# Sheet2.net
KiCad netlist of a schematic drawn in Altium Designer
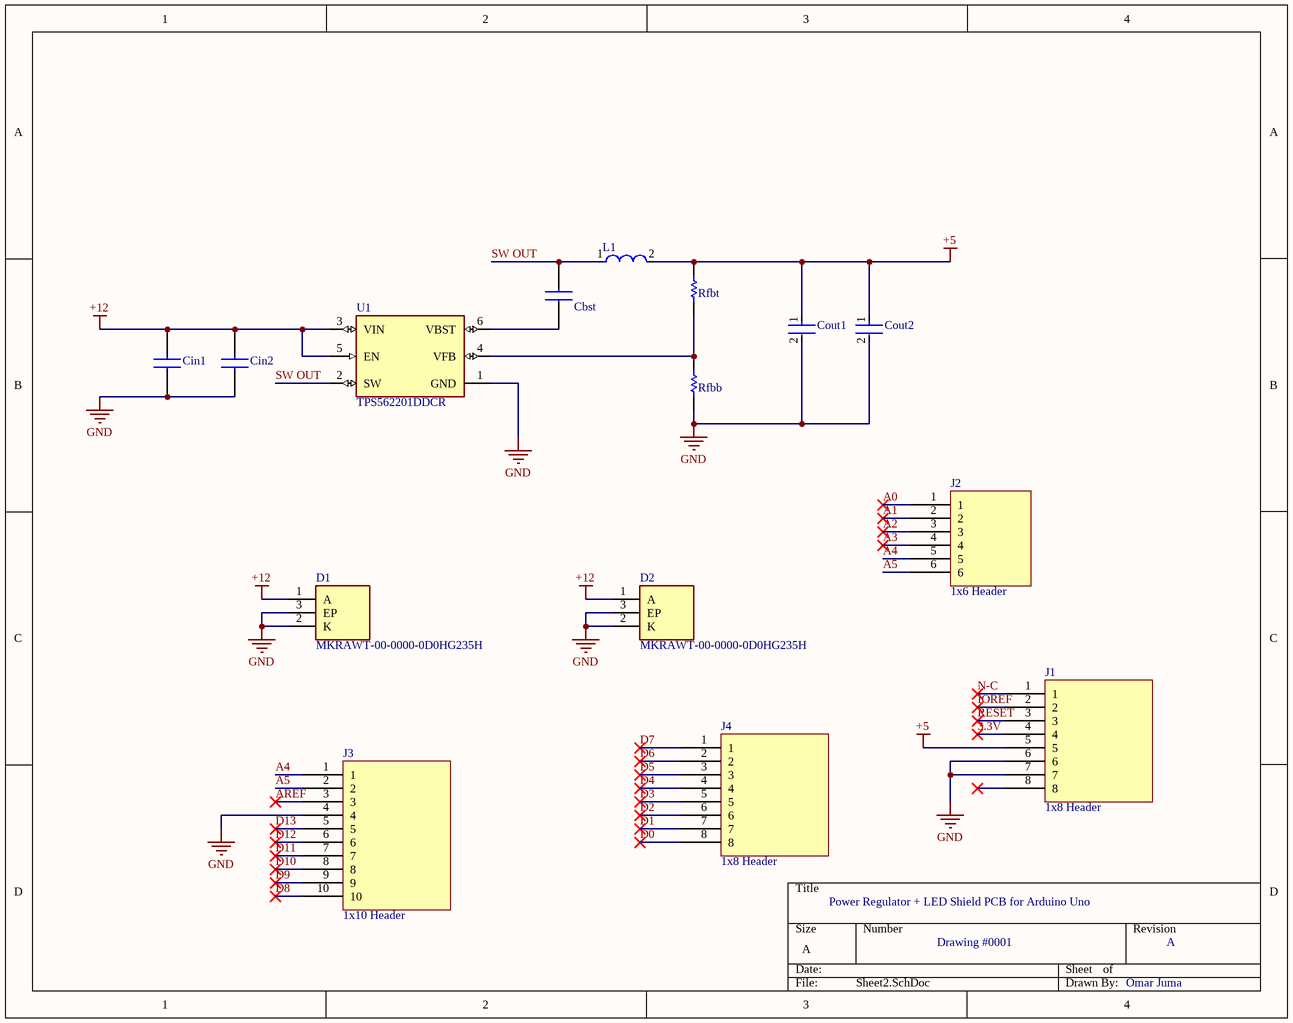
[diagram p0: Sheet2.SchDoc]

(export (version "E")
  (design (tool "Eeschema 10.0.6"))
  (components
    (comp (ref "Cbst")
      (value "08053C104KAT2A")
      (footprint "CAPC2012X94N")
      (libsource (lib "08053C104KAT2A") (part "08053C104KAT2A"))
    )
    (comp (ref "Cin1")
      (value "MSAST219LB5106KTNA01")
      (footprint "CAPC2114X95N")
      (description "Multilayer Ceramic Capacitors MLCC - SMD/SMT 25V 10uF X5R 0805 10%")
      (libsource (lib "MSAST219LB5106KTNA01") (part "MSAST219LB5106KTNA01"))
    )
    (comp (ref "Cin2")
      (value "MSAST219LB5106KTNA01")
      (footprint "CAPC2114X95N")
      (description "Multilayer Ceramic Capacitors MLCC - SMD/SMT 25V 10uF X5R 0805 10%")
      (libsource (lib "MSAST219LB5106KTNA01") (part "MSAST219LB5106KTNA01"))
    )
    (comp (ref "Cout1")
      (value "GRM21BR61A226ME44L")
      (footprint "FP-GRM21B-0_2-e0_2_0_7-IPC_C")
      (description "Chip Multilayer Ceramic Capacitors for General Purpose, 0805, 22uF, X5R, 15%, 20%, 10V")
      (fields (field (name "TOLERANCE") "20%") (field (name "VOLTAGE") "10V"))
      (libsource (lib "Altium Content Vault") (part "b4654b650e69147ec39a6b967a45e02"))
    )
    (comp (ref "Cout2")
      (value "GRM21BR61A226ME44L")
      (footprint "FP-GRM21B-0_2-e0_2_0_7-IPC_C")
      (description "Chip Multilayer Ceramic Capacitors for General Purpose, 0805, 22uF, X5R, 15%, 20%, 10V")
      (fields (field (name "TOLERANCE") "20%") (field (name "VOLTAGE") "10V"))
      (libsource (lib "Altium Content Vault") (part "b4654b650e69147ec39a6b967a45e02"))
    )
    (comp (ref "D1")
      (value "MKRAWT-00-0000-0D0HG235H")
      (footprint "MKRAWT0000000D0HG235H")
      (description "LED Uni-Color White 3500K 80 2-Pin SMD EP T/R")
      (fields (field (name "MOUSER PART NUMBER") "941-MKRAWT0D0HG235H"))
      (libsource (lib "MKRAWT-00-0000-0D0HG235H") (part "MKRAWT-00-0000-0D0HG235H"))
    )
    (comp (ref "D2")
      (value "MKRAWT-00-0000-0D0HG235H")
      (footprint "MKRAWT0000000D0HG235H")
      (description "LED Uni-Color White 3500K 80 2-Pin SMD EP T/R")
      (fields (field (name "MOUSER PART NUMBER") "941-MKRAWT0D0HG235H"))
      (libsource (lib "MKRAWT-00-0000-0D0HG235H") (part "MKRAWT-00-0000-0D0HG235H"))
    )
    (comp (ref "J1")
      (value "1x8 Header")
      (footprint "1x8 Header")
      (libsource (lib "Arduino_Headers") (part "1x8 Header"))
    )
    (comp (ref "J2")
      (value "1x6 Header")
      (footprint "1x6 Header")
      (libsource (lib "Arduino_Headers") (part "1x6 Header"))
    )
    (comp (ref "J3")
      (value "1x10 Header")
      (footprint "1x10 Header")
      (libsource (lib "Arduino_Headers") (part "1x10 Header"))
    )
    (comp (ref "J4")
      (value "1x8 Header")
      (footprint "1x8 Header")
      (libsource (lib "Arduino_Headers") (part "1x8 Header"))
    )
    (comp (ref "L1")
      (value "NRS8030T3R3MJGJ")
      (footprint "FP-NRS8030-MFG")
      (description "Inductor Power Shielded Wirewound 3.3uH 20% 100KHz Ferrite 4.2A 24.7mΩ DCR T/R")
      (fields (field (name "TOLERANCE") "20%"))
      (libsource (lib "Altium Content Vault") (part "725321dda6339637d4d059423bc1c3c"))
    )
    (comp (ref "Rfbb")
      (value "ERJ2RKF1002X")
      (footprint "RESC1005X40X25LL05T05")
      (description "Chip Resistor, 10 KOhm, +/- 1%, 0.1 W, -55 to 155 degC, 0402 (1005 Metric), RoHS, Tape and Reel")
      (fields (field (name "TOLERANCE") "1%") (field (name "MANUFACTURER") "Panasonic"))
      (libsource (lib "Altium Content Vault") (part "RES-2"))
    )
    (comp (ref "Rfbt")
      (value "CRCW020156K2FNED")
      (footprint "RESC0603X28X15NL05T05")
      (fields (field (name "MANUFACTURER") "Vishay Dale"))
      (libsource (lib "Altium Content Vault") (part "RES"))
    )
    (comp (ref "U1")
      (value "TPS562201DDCR")
      (footprint "FP-DDC0006A-IPC_C")
      (description "IC REG BUCK ADJ 2A TSOT23-6")
      (libsource (lib "Altium Content Vault") (part "957e164956730ea4bf6293280af19fc"))
    )
  )
  (nets
    (net (code "1") (name "+5") (class "Default")
      (node (ref "Cout1") (pin "1") (pinfunction "1_1") (pintype "passive"))
      (node (ref "Cout2") (pin "1") (pinfunction "1_1") (pintype "passive"))
      (node (ref "J1") (pin "5") (pinfunction "5_5") (pintype "passive"))
      (node (ref "L1") (pin "2") (pinfunction "2_2") (pintype "passive"))
      (node (ref "Rfbt") (pin "2") (pinfunction "2_2") (pintype "passive"))
    )
    (net (code "2") (name "+12") (class "Default")
      (node (ref "Cin1") (pin "2") (pinfunction "2_2") (pintype "passive"))
      (node (ref "Cin2") (pin "2") (pinfunction "2_2") (pintype "passive"))
      (node (ref "D1") (pin "1") (pinfunction "A_1") (pintype "passive"))
      (node (ref "D2") (pin "1") (pinfunction "A_1") (pintype "passive"))
      (node (ref "U1") (pin "3") (pinfunction "VIN_3") (pintype "bidirectional"))
      (node (ref "U1") (pin "5") (pinfunction "EN_5") (pintype "input"))
    )
    (net (code "3") (name "/3.3V") (class "Default")
      (node (ref "J1") (pin "4") (pinfunction "4_4") (pintype "passive+no_connect"))
    )
    (net (code "4") (name "/A0") (class "Default")
      (node (ref "J2") (pin "1") (pinfunction "1_1") (pintype "passive+no_connect"))
    )
    (net (code "5") (name "/A1") (class "Default")
      (node (ref "J2") (pin "2") (pinfunction "2_2") (pintype "passive+no_connect"))
    )
    (net (code "6") (name "/A2") (class "Default")
      (node (ref "J2") (pin "3") (pinfunction "3_3") (pintype "passive+no_connect"))
    )
    (net (code "7") (name "/A3") (class "Default")
      (node (ref "J2") (pin "4") (pinfunction "4_4") (pintype "passive+no_connect"))
    )
    (net (code "8") (name "/A4") (class "Default")
      (node (ref "J2") (pin "5") (pinfunction "5_5") (pintype "passive"))
      (node (ref "J3") (pin "1") (pinfunction "1_1") (pintype "passive"))
    )
    (net (code "9") (name "/A5") (class "Default")
      (node (ref "J2") (pin "6") (pinfunction "6_6") (pintype "passive"))
      (node (ref "J3") (pin "2") (pinfunction "2_2") (pintype "passive"))
    )
    (net (code "10") (name "/AREF") (class "Default")
      (node (ref "J3") (pin "3") (pinfunction "3_3") (pintype "passive+no_connect"))
    )
    (net (code "11") (name "/D0") (class "Default")
      (node (ref "J4") (pin "8") (pinfunction "8_8") (pintype "passive+no_connect"))
    )
    (net (code "12") (name "/D1") (class "Default")
      (node (ref "J4") (pin "7") (pinfunction "7_7") (pintype "passive+no_connect"))
    )
    (net (code "13") (name "/D2") (class "Default")
      (node (ref "J4") (pin "6") (pinfunction "6_6") (pintype "passive+no_connect"))
    )
    (net (code "14") (name "/D3") (class "Default")
      (node (ref "J4") (pin "5") (pinfunction "5_5") (pintype "passive+no_connect"))
    )
    (net (code "15") (name "/D4") (class "Default")
      (node (ref "J4") (pin "4") (pinfunction "4_4") (pintype "passive+no_connect"))
    )
    (net (code "16") (name "/D5") (class "Default")
      (node (ref "J4") (pin "3") (pinfunction "3_3") (pintype "passive+no_connect"))
    )
    (net (code "17") (name "/D6") (class "Default")
      (node (ref "J4") (pin "2") (pinfunction "2_2") (pintype "passive+no_connect"))
    )
    (net (code "18") (name "/D7") (class "Default")
      (node (ref "J4") (pin "1") (pinfunction "1_1") (pintype "passive+no_connect"))
    )
    (net (code "19") (name "/D8") (class "Default")
      (node (ref "J3") (pin "10") (pinfunction "10_10") (pintype "passive+no_connect"))
    )
    (net (code "20") (name "/D9") (class "Default")
      (node (ref "J3") (pin "9") (pinfunction "9_9") (pintype "passive+no_connect"))
    )
    (net (code "21") (name "/D10") (class "Default")
      (node (ref "J3") (pin "8") (pinfunction "8_8") (pintype "passive+no_connect"))
    )
    (net (code "22") (name "/D11") (class "Default")
      (node (ref "J3") (pin "7") (pinfunction "7_7") (pintype "passive+no_connect"))
    )
    (net (code "23") (name "/D12") (class "Default")
      (node (ref "J3") (pin "6") (pinfunction "6_6") (pintype "passive+no_connect"))
    )
    (net (code "24") (name "/D13") (class "Default")
      (node (ref "J3") (pin "5") (pinfunction "5_5") (pintype "passive+no_connect"))
    )
    (net (code "25") (name "/IOREF") (class "Default")
      (node (ref "J1") (pin "2") (pinfunction "2_2") (pintype "passive+no_connect"))
    )
    (net (code "26") (name "/N-C") (class "Default")
      (node (ref "J1") (pin "1") (pinfunction "1_1") (pintype "passive+no_connect"))
    )
    (net (code "27") (name "/RESET") (class "Default")
      (node (ref "J1") (pin "3") (pinfunction "3_3") (pintype "passive+no_connect"))
    )
    (net (code "28") (name "/SW OUT") (class "Default")
      (node (ref "Cbst") (pin "2") (pinfunction "2_2") (pintype "passive"))
      (node (ref "L1") (pin "1") (pinfunction "1_1") (pintype "passive"))
      (node (ref "U1") (pin "2") (pinfunction "SW_2") (pintype "bidirectional"))
    )
    (net (code "29") (name "GND") (class "Default")
      (node (ref "Cin1") (pin "1") (pinfunction "1_1") (pintype "passive"))
      (node (ref "Cin2") (pin "1") (pinfunction "1_1") (pintype "passive"))
      (node (ref "Cout1") (pin "2") (pinfunction "2_2") (pintype "passive"))
      (node (ref "Cout2") (pin "2") (pinfunction "2_2") (pintype "passive"))
      (node (ref "D1") (pin "2") (pinfunction "K_2") (pintype "passive"))
      (node (ref "D1") (pin "3") (pinfunction "EP_3") (pintype "passive"))
      (node (ref "D2") (pin "2") (pinfunction "K_2") (pintype "passive"))
      (node (ref "D2") (pin "3") (pinfunction "EP_3") (pintype "passive"))
      (node (ref "J1") (pin "6") (pinfunction "6_6") (pintype "passive"))
      (node (ref "J1") (pin "7") (pinfunction "7_7") (pintype "passive"))
      (node (ref "J3") (pin "4") (pinfunction "4_4") (pintype "passive"))
      (node (ref "Rfbb") (pin "1") (pinfunction "1_1") (pintype "passive"))
      (node (ref "U1") (pin "1") (pinfunction "GND_1") (pintype "power_in"))
    )
    (net (code "30") (name "Net-(U1-VBST)") (class "Default")
      (node (ref "Cbst") (pin "1") (pinfunction "1_1") (pintype "passive"))
      (node (ref "U1") (pin "6") (pinfunction "VBST_6") (pintype "bidirectional"))
    )
    (net (code "31") (name "Net-(U1-VFB)") (class "Default")
      (node (ref "Rfbb") (pin "2") (pinfunction "2_2") (pintype "passive"))
      (node (ref "Rfbt") (pin "1") (pinfunction "1_1") (pintype "passive"))
      (node (ref "U1") (pin "4") (pinfunction "VFB_4") (pintype "bidirectional"))
    )
    (net (code "32") (name "unconnected-(J1-Pad8)") (class "Default")
      (node (ref "J1") (pin "8") (pinfunction "8_8") (pintype "passive+no_connect"))
    )
  )
)
